# Kit_Sumo_Bot_Final.net
KiCad netlist of a schematic drawn in EasyEDA
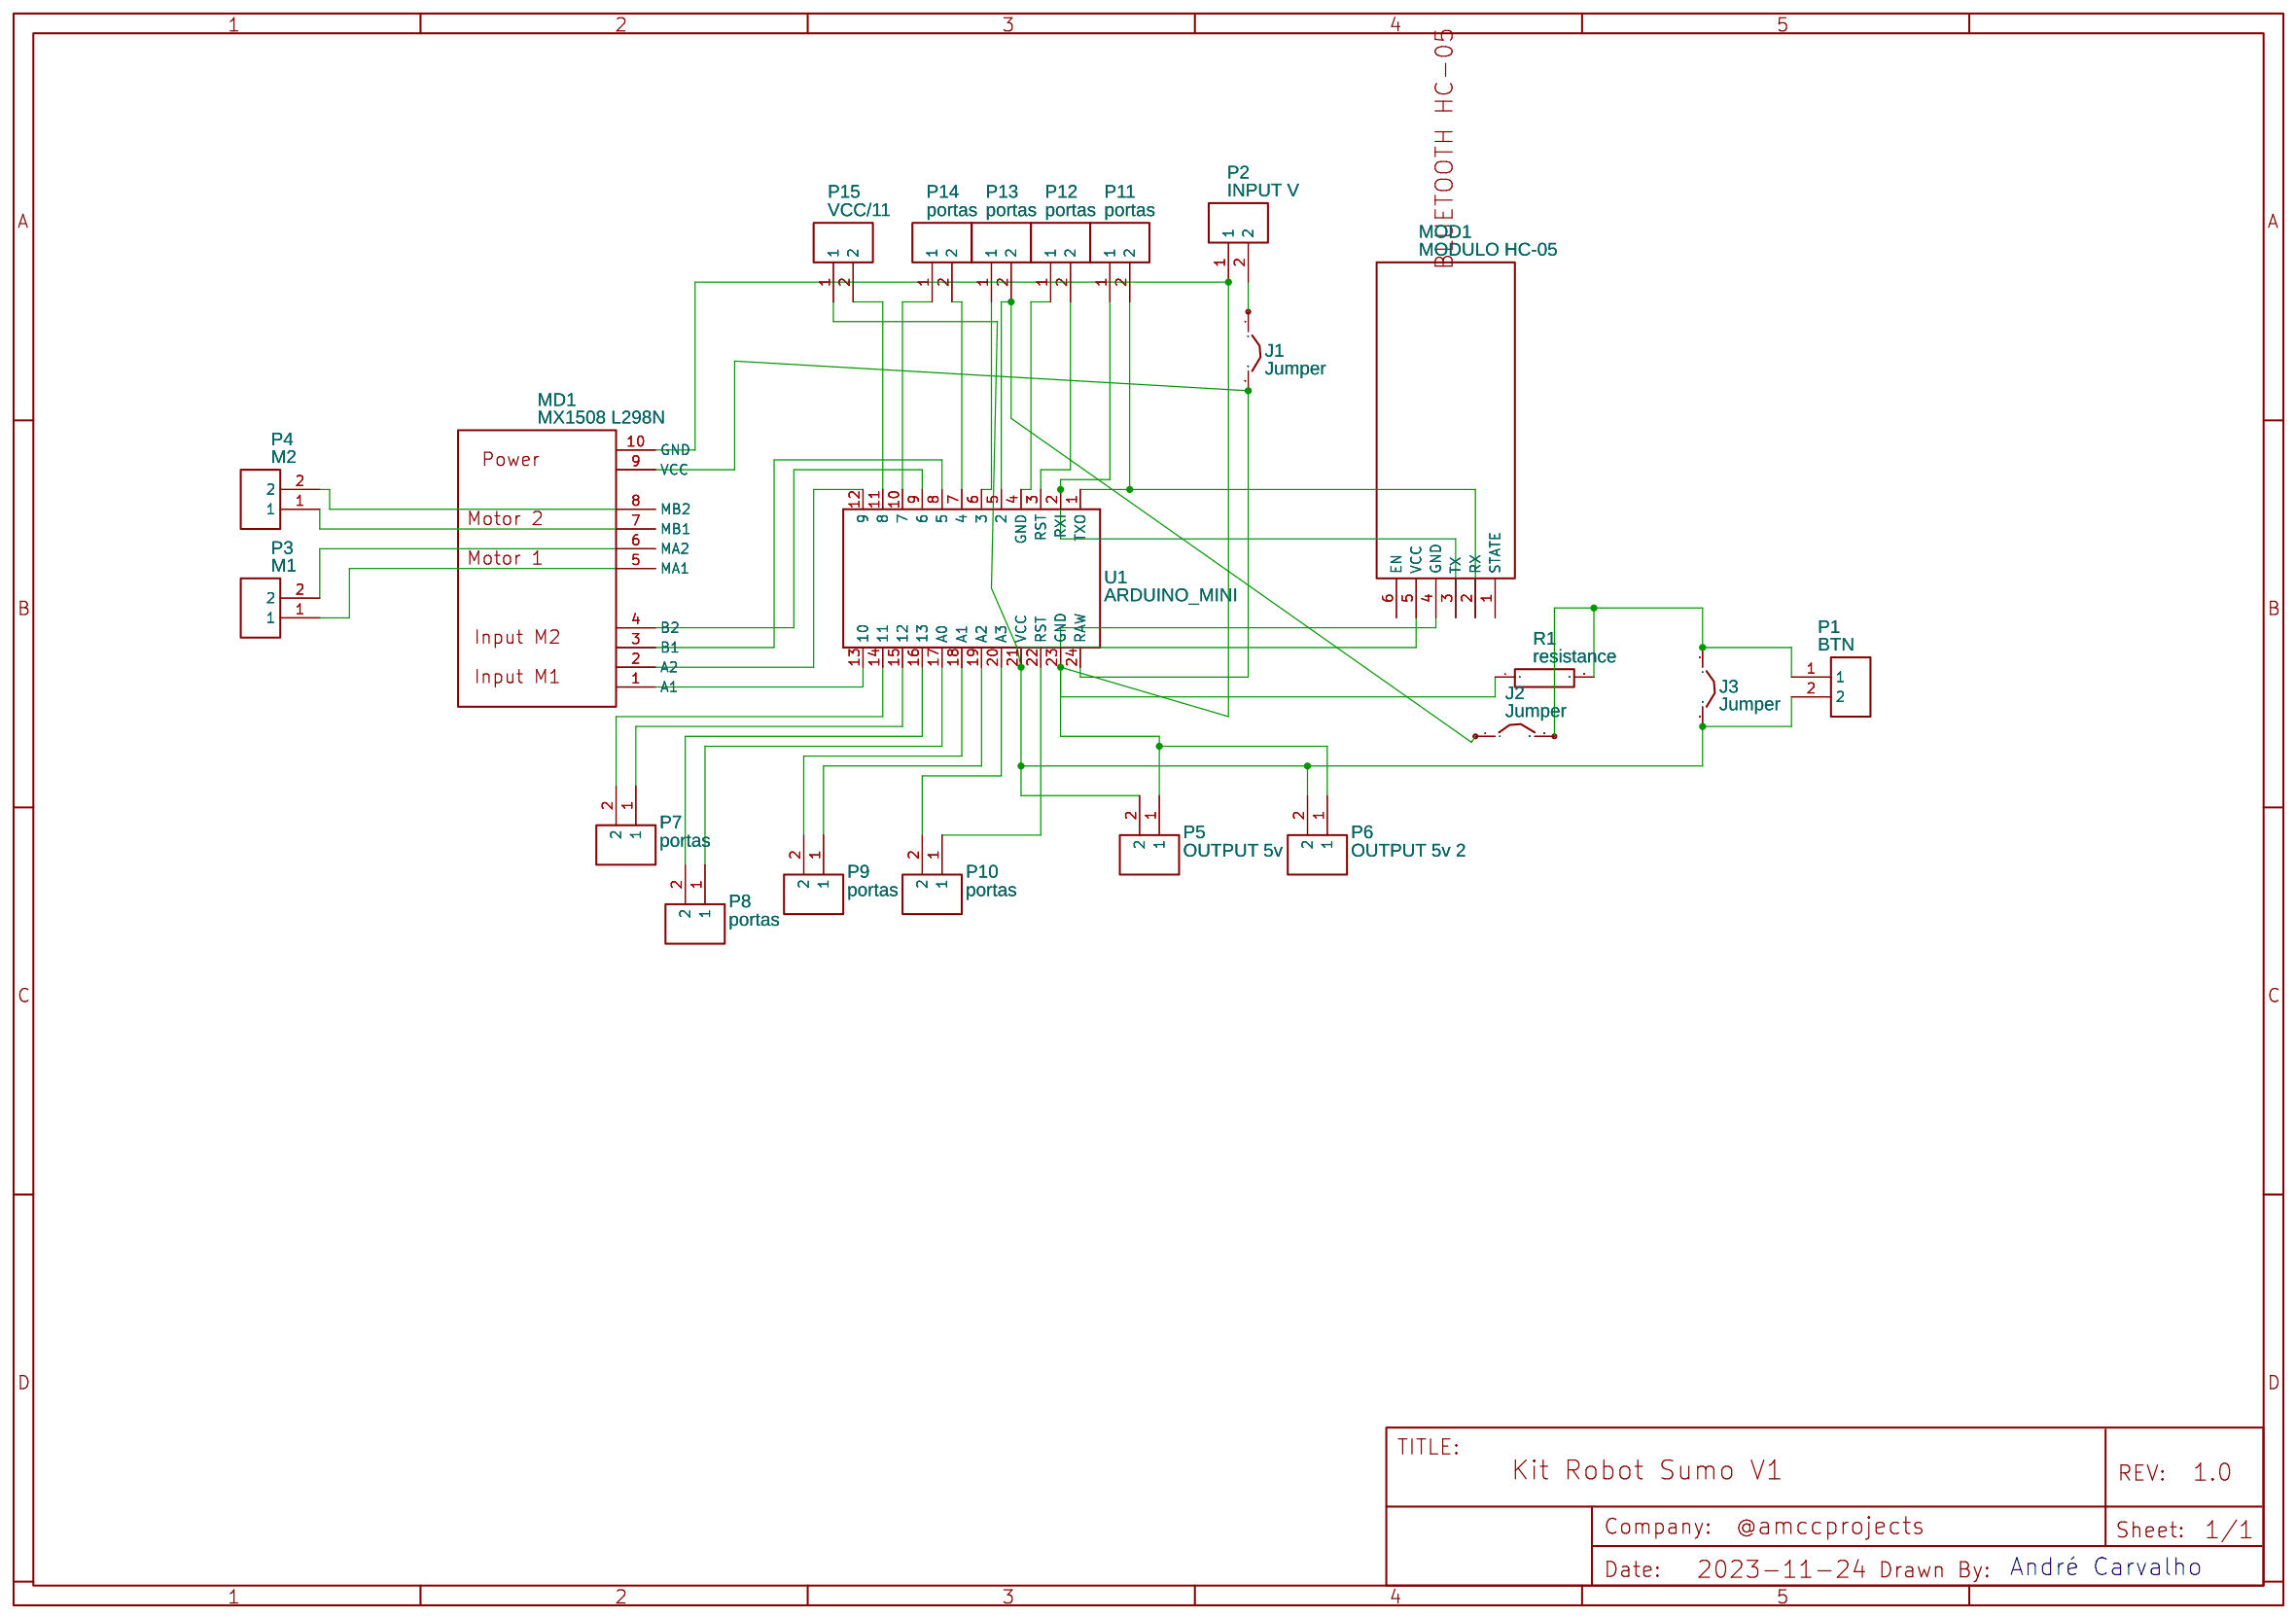
[diagram p0: schematic sheet]

(export (version "E")
  (design (tool "Eeschema 10.0.6"))
  (components
    (comp (ref "J1")
      (value "Jumper")
      (fields (field (name "Manufacturer Part") "NONE"))
      (libsource (lib "") (part "Jumper"))
    )
    (comp (ref "J2")
      (value "Jumper")
      (fields (field (name "Manufacturer Part") "NONE"))
      (libsource (lib "") (part "Jumper_1"))
    )
    (comp (ref "J3")
      (value "Jumper")
      (fields (field (name "Manufacturer Part") "NONE"))
      (libsource (lib "") (part "Jumper"))
    )
    (comp (ref "MD1") (value "MX1508 L298N") (libsource (lib "") (part "ZS-PWM MX1508 L298N PWM Module")))
    (comp (ref "MOD1") (value "MODULO HC-05") (libsource (lib "") (part "MODULO HC-05")))
    (comp (ref "P1")
      (value "BTN")
      (fields
        (field (name "Manufacturer Part") "WJ500V-5.08-2P")
        (field (name "Manufacturer") "KANGNEX(康奈克斯电气)")
      )
      (libsource (lib "") (part "WJ500V-5.08-2P-14-00A_3"))
    )
    (comp (ref "P2")
      (value "INPUT V")
      (fields
        (field (name "Manufacturer Part") "WJ500V-5.08-2P")
        (field (name "Manufacturer") "KANGNEX(康奈克斯电气)")
      )
      (libsource (lib "") (part "WJ500V-5.08-2P-14-00A_1"))
    )
    (comp (ref "P3")
      (value "M1")
      (fields
        (field (name "Manufacturer Part") "WJ500V-5.08-2P")
        (field (name "Manufacturer") "KANGNEX(康奈克斯电气)")
      )
      (libsource (lib "") (part "WJ500V-5.08-2P-14-00A_2"))
    )
    (comp (ref "P4")
      (value "M2")
      (fields
        (field (name "Manufacturer Part") "WJ500V-5.08-2P")
        (field (name "Manufacturer") "KANGNEX(康奈克斯电气)")
      )
      (libsource (lib "") (part "WJ500V-5.08-2P-14-00A_2"))
    )
    (comp (ref "P5")
      (value "OUTPUT 5v")
      (fields
        (field (name "Manufacturer Part") "WJ500V-5.08-2P")
        (field (name "Manufacturer") "KANGNEX(康奈克斯电气)")
      )
      (libsource (lib "") (part "WJ500V-5.08-2P-14-00A"))
    )
    (comp (ref "P6")
      (value "OUTPUT 5v 2")
      (fields
        (field (name "Manufacturer Part") "WJ500V-5.08-2P")
        (field (name "Manufacturer") "KANGNEX(康奈克斯电气)")
      )
      (libsource (lib "") (part "WJ500V-5.08-2P-14-00A"))
    )
    (comp (ref "P7")
      (value "portas")
      (fields
        (field (name "Manufacturer Part") "WJ500V-5.08-2P")
        (field (name "Manufacturer") "KANGNEX(康奈克斯电气)")
      )
      (libsource (lib "") (part "WJ500V-5.08-2P-14-00A"))
    )
    (comp (ref "P8")
      (value "portas")
      (fields
        (field (name "Manufacturer Part") "WJ500V-5.08-2P")
        (field (name "Manufacturer") "KANGNEX(康奈克斯电气)")
      )
      (libsource (lib "") (part "WJ500V-5.08-2P-14-00A"))
    )
    (comp (ref "P9")
      (value "portas")
      (fields
        (field (name "Manufacturer Part") "WJ500V-5.08-2P")
        (field (name "Manufacturer") "KANGNEX(康奈克斯电气)")
      )
      (libsource (lib "") (part "WJ500V-5.08-2P-14-00A"))
    )
    (comp (ref "P10")
      (value "portas")
      (fields
        (field (name "Manufacturer Part") "WJ500V-5.08-2P")
        (field (name "Manufacturer") "KANGNEX(康奈克斯电气)")
      )
      (libsource (lib "") (part "WJ500V-5.08-2P-14-00A"))
    )
    (comp (ref "P11")
      (value "portas")
      (fields
        (field (name "Manufacturer Part") "WJ500V-5.08-2P")
        (field (name "Manufacturer") "KANGNEX(康奈克斯电气)")
      )
      (libsource (lib "") (part "WJ500V-5.08-2P-14-00A_1"))
    )
    (comp (ref "P12")
      (value "portas")
      (fields
        (field (name "Manufacturer Part") "WJ500V-5.08-2P")
        (field (name "Manufacturer") "KANGNEX(康奈克斯电气)")
      )
      (libsource (lib "") (part "WJ500V-5.08-2P-14-00A_1"))
    )
    (comp (ref "P13")
      (value "portas")
      (fields
        (field (name "Manufacturer Part") "WJ500V-5.08-2P")
        (field (name "Manufacturer") "KANGNEX(康奈克斯电气)")
      )
      (libsource (lib "") (part "WJ500V-5.08-2P-14-00A_1"))
    )
    (comp (ref "P14")
      (value "portas")
      (fields
        (field (name "Manufacturer Part") "WJ500V-5.08-2P")
        (field (name "Manufacturer") "KANGNEX(康奈克斯电气)")
      )
      (libsource (lib "") (part "WJ500V-5.08-2P-14-00A_1"))
    )
    (comp (ref "P15")
      (value "VCC/11")
      (fields
        (field (name "Manufacturer Part") "WJ500V-5.08-2P")
        (field (name "Manufacturer") "KANGNEX(康奈克斯电气)")
      )
      (libsource (lib "") (part "WJ500V-5.08-2P-14-00A_1"))
    )
    (comp (ref "R1") (value "resistance") (libsource (lib "") (part "resistance")))
    (comp (ref "U1") (value "ARDUINO_MINI") (libsource (lib "") (part "ARDUINO_MINI")))
  )
  (nets
    (net (code "1") (name "Net-(J1-Pad1)") (class "Default")
      (node (ref "J1") (pin "1") (pinfunction "1_1") (pintype "unspecified"))
      (node (ref "P2") (pin "2") (pinfunction "2_2") (pintype "unspecified"))
    )
    (net (code "2") (name "Net-(J2-Pad2)") (class "Default")
      (node (ref "J2") (pin "2") (pinfunction "2_2") (pintype "unspecified"))
      (node (ref "J3") (pin "1") (pinfunction "1_1") (pintype "unspecified"))
      (node (ref "P1") (pin "1") (pinfunction "1_1") (pintype "unspecified"))
      (node (ref "R1") (pin "2") (pinfunction "2_2") (pintype "unspecified"))
    )
    (net (code "3") (name "Net-(MD1-A1)") (class "Default")
      (node (ref "MD1") (pin "1") (pinfunction "A1_1") (pintype "input"))
      (node (ref "U1") (pin "13") (pinfunction "10_13") (pintype "unspecified"))
    )
    (net (code "4") (name "Net-(MD1-A2)") (class "Default")
      (node (ref "MD1") (pin "2") (pinfunction "A2_2") (pintype "input"))
      (node (ref "U1") (pin "12") (pinfunction "9_12") (pintype "unspecified"))
    )
    (net (code "5") (name "Net-(MD1-B1)") (class "Default")
      (node (ref "MD1") (pin "3") (pinfunction "B1_3") (pintype "input"))
      (node (ref "U1") (pin "8") (pinfunction "5_8") (pintype "unspecified"))
    )
    (net (code "6") (name "Net-(MD1-B2)") (class "Default")
      (node (ref "MD1") (pin "4") (pinfunction "B2_4") (pintype "input"))
      (node (ref "U1") (pin "9") (pinfunction "6_9") (pintype "unspecified"))
    )
    (net (code "7") (name "Net-(MD1-GND)") (class "Default")
      (node (ref "MD1") (pin "10") (pinfunction "GND_10") (pintype "passive"))
      (node (ref "MOD1") (pin "4") (pinfunction "GND_4") (pintype "unspecified"))
      (node (ref "P2") (pin "1") (pinfunction "1_1") (pintype "unspecified"))
      (node (ref "P5") (pin "1") (pinfunction "1_1") (pintype "unspecified"))
      (node (ref "P6") (pin "1") (pinfunction "1_1") (pintype "unspecified"))
      (node (ref "R1") (pin "1") (pinfunction "1_1") (pintype "unspecified"))
      (node (ref "U1") (pin "23") (pinfunction "GND_23") (pintype "unspecified"))
    )
    (net (code "8") (name "Net-(MD1-MA1)") (class "Default")
      (node (ref "MD1") (pin "5") (pinfunction "MA1_5") (pintype "output"))
      (node (ref "P3") (pin "1") (pinfunction "1_1") (pintype "unspecified"))
    )
    (net (code "9") (name "Net-(MD1-MA2)") (class "Default")
      (node (ref "MD1") (pin "6") (pinfunction "MA2_6") (pintype "output"))
      (node (ref "P3") (pin "2") (pinfunction "2_2") (pintype "unspecified"))
    )
    (net (code "10") (name "Net-(MD1-MB1)") (class "Default")
      (node (ref "MD1") (pin "7") (pinfunction "MB1_7") (pintype "output"))
      (node (ref "P4") (pin "1") (pinfunction "1_1") (pintype "unspecified"))
    )
    (net (code "11") (name "Net-(MD1-MB2)") (class "Default")
      (node (ref "MD1") (pin "8") (pinfunction "MB2_8") (pintype "output"))
      (node (ref "P4") (pin "2") (pinfunction "2_2") (pintype "unspecified"))
    )
    (net (code "12") (name "Net-(MD1-VCC)") (class "Default")
      (node (ref "J1") (pin "2") (pinfunction "2_2") (pintype "unspecified"))
      (node (ref "MD1") (pin "9") (pinfunction "VCC_9") (pintype "passive"))
      (node (ref "U1") (pin "24") (pinfunction "RAW_24") (pintype "unspecified"))
    )
    (net (code "13") (name "Net-(MOD1-RX)") (class "Default")
      (node (ref "MOD1") (pin "2") (pinfunction "RX_2") (pintype "unspecified"))
      (node (ref "P11") (pin "2") (pinfunction "2_2") (pintype "unspecified"))
      (node (ref "U1") (pin "1") (pinfunction "TXO_1") (pintype "unspecified"))
    )
    (net (code "14") (name "Net-(MOD1-TX)") (class "Default")
      (node (ref "MOD1") (pin "3") (pinfunction "TX_3") (pintype "unspecified"))
      (node (ref "P11") (pin "1") (pinfunction "1_1") (pintype "unspecified"))
      (node (ref "U1") (pin "2") (pinfunction "RXI_2") (pintype "unspecified"))
    )
    (net (code "15") (name "Net-(MOD1-VCC)") (class "Default")
      (node (ref "J3") (pin "2") (pinfunction "2_2") (pintype "unspecified"))
      (node (ref "MOD1") (pin "5") (pinfunction "VCC_5") (pintype "unspecified"))
      (node (ref "P1") (pin "2") (pinfunction "2_2") (pintype "unspecified"))
      (node (ref "P15") (pin "1") (pinfunction "1_1") (pintype "unspecified"))
      (node (ref "P5") (pin "2") (pinfunction "2_2") (pintype "unspecified"))
      (node (ref "P6") (pin "2") (pinfunction "2_2") (pintype "unspecified"))
      (node (ref "U1") (pin "21") (pinfunction "VCC_21") (pintype "unspecified"))
    )
    (net (code "16") (name "Net-(P10-Pad1)") (class "Default")
      (node (ref "P10") (pin "1") (pinfunction "1_1") (pintype "unspecified"))
      (node (ref "U1") (pin "22") (pinfunction "RST_22") (pintype "unspecified"))
    )
    (net (code "17") (name "Net-(P12-Pad1)") (class "Default")
      (node (ref "P12") (pin "1") (pinfunction "1_1") (pintype "unspecified"))
      (node (ref "U1") (pin "4") (pinfunction "GND_4") (pintype "unspecified"))
    )
    (net (code "18") (name "Net-(P12-Pad2)") (class "Default")
      (node (ref "P12") (pin "2") (pinfunction "2_2") (pintype "unspecified"))
      (node (ref "U1") (pin "3") (pinfunction "RST_3") (pintype "unspecified"))
    )
    (net (code "19") (name "Net-(U1-2)") (class "Default")
      (node (ref "J2") (pin "1") (pinfunction "1_1") (pintype "unspecified"))
      (node (ref "P13") (pin "2") (pinfunction "2_2") (pintype "unspecified"))
      (node (ref "U1") (pin "5") (pinfunction "2_5") (pintype "unspecified"))
    )
    (net (code "20") (name "Net-(U1-3)") (class "Default")
      (node (ref "P13") (pin "1") (pinfunction "1_1") (pintype "unspecified"))
      (node (ref "U1") (pin "6") (pinfunction "3_6") (pintype "unspecified"))
    )
    (net (code "21") (name "Net-(U1-4)") (class "Default")
      (node (ref "P14") (pin "2") (pinfunction "2_2") (pintype "unspecified"))
      (node (ref "U1") (pin "7") (pinfunction "4_7") (pintype "unspecified"))
    )
    (net (code "22") (name "Net-(U1-7)") (class "Default")
      (node (ref "P14") (pin "1") (pinfunction "1_1") (pintype "unspecified"))
      (node (ref "U1") (pin "10") (pinfunction "7_10") (pintype "unspecified"))
    )
    (net (code "23") (name "Net-(U1-8)") (class "Default")
      (node (ref "P15") (pin "2") (pinfunction "2_2") (pintype "unspecified"))
      (node (ref "U1") (pin "11") (pinfunction "8_11") (pintype "unspecified"))
    )
    (net (code "24") (name "Net-(U1-11)") (class "Default")
      (node (ref "P7") (pin "2") (pinfunction "2_2") (pintype "unspecified"))
      (node (ref "U1") (pin "14") (pinfunction "11_14") (pintype "unspecified"))
    )
    (net (code "25") (name "Net-(U1-12)") (class "Default")
      (node (ref "P7") (pin "1") (pinfunction "1_1") (pintype "unspecified"))
      (node (ref "U1") (pin "15") (pinfunction "12_15") (pintype "unspecified"))
    )
    (net (code "26") (name "Net-(U1-13)") (class "Default")
      (node (ref "P8") (pin "2") (pinfunction "2_2") (pintype "unspecified"))
      (node (ref "U1") (pin "16") (pinfunction "13_16") (pintype "unspecified"))
    )
    (net (code "27") (name "Net-(U1-A0)") (class "Default")
      (node (ref "P8") (pin "1") (pinfunction "1_1") (pintype "unspecified"))
      (node (ref "U1") (pin "17") (pinfunction "A0_17") (pintype "unspecified"))
    )
    (net (code "28") (name "Net-(U1-A1)") (class "Default")
      (node (ref "P9") (pin "2") (pinfunction "2_2") (pintype "unspecified"))
      (node (ref "U1") (pin "18") (pinfunction "A1_18") (pintype "unspecified"))
    )
    (net (code "29") (name "Net-(U1-A2)") (class "Default")
      (node (ref "P9") (pin "1") (pinfunction "1_1") (pintype "unspecified"))
      (node (ref "U1") (pin "19") (pinfunction "A2_19") (pintype "unspecified"))
    )
    (net (code "30") (name "Net-(U1-A3)") (class "Default")
      (node (ref "P10") (pin "2") (pinfunction "2_2") (pintype "unspecified"))
      (node (ref "U1") (pin "20") (pinfunction "A3_20") (pintype "unspecified"))
    )
    (net (code "31") (name "unconnected-(MOD1-EN-Pad6)") (class "Default")
      (node (ref "MOD1") (pin "6") (pinfunction "EN_6") (pintype "unspecified"))
    )
    (net (code "32") (name "unconnected-(MOD1-STATE-Pad1)") (class "Default")
      (node (ref "MOD1") (pin "1") (pinfunction "STATE_1") (pintype "unspecified"))
    )
  )
)
